# I2C_LCD_Backpack.net
KiCad netlist of a schematic drawn in EAGLE
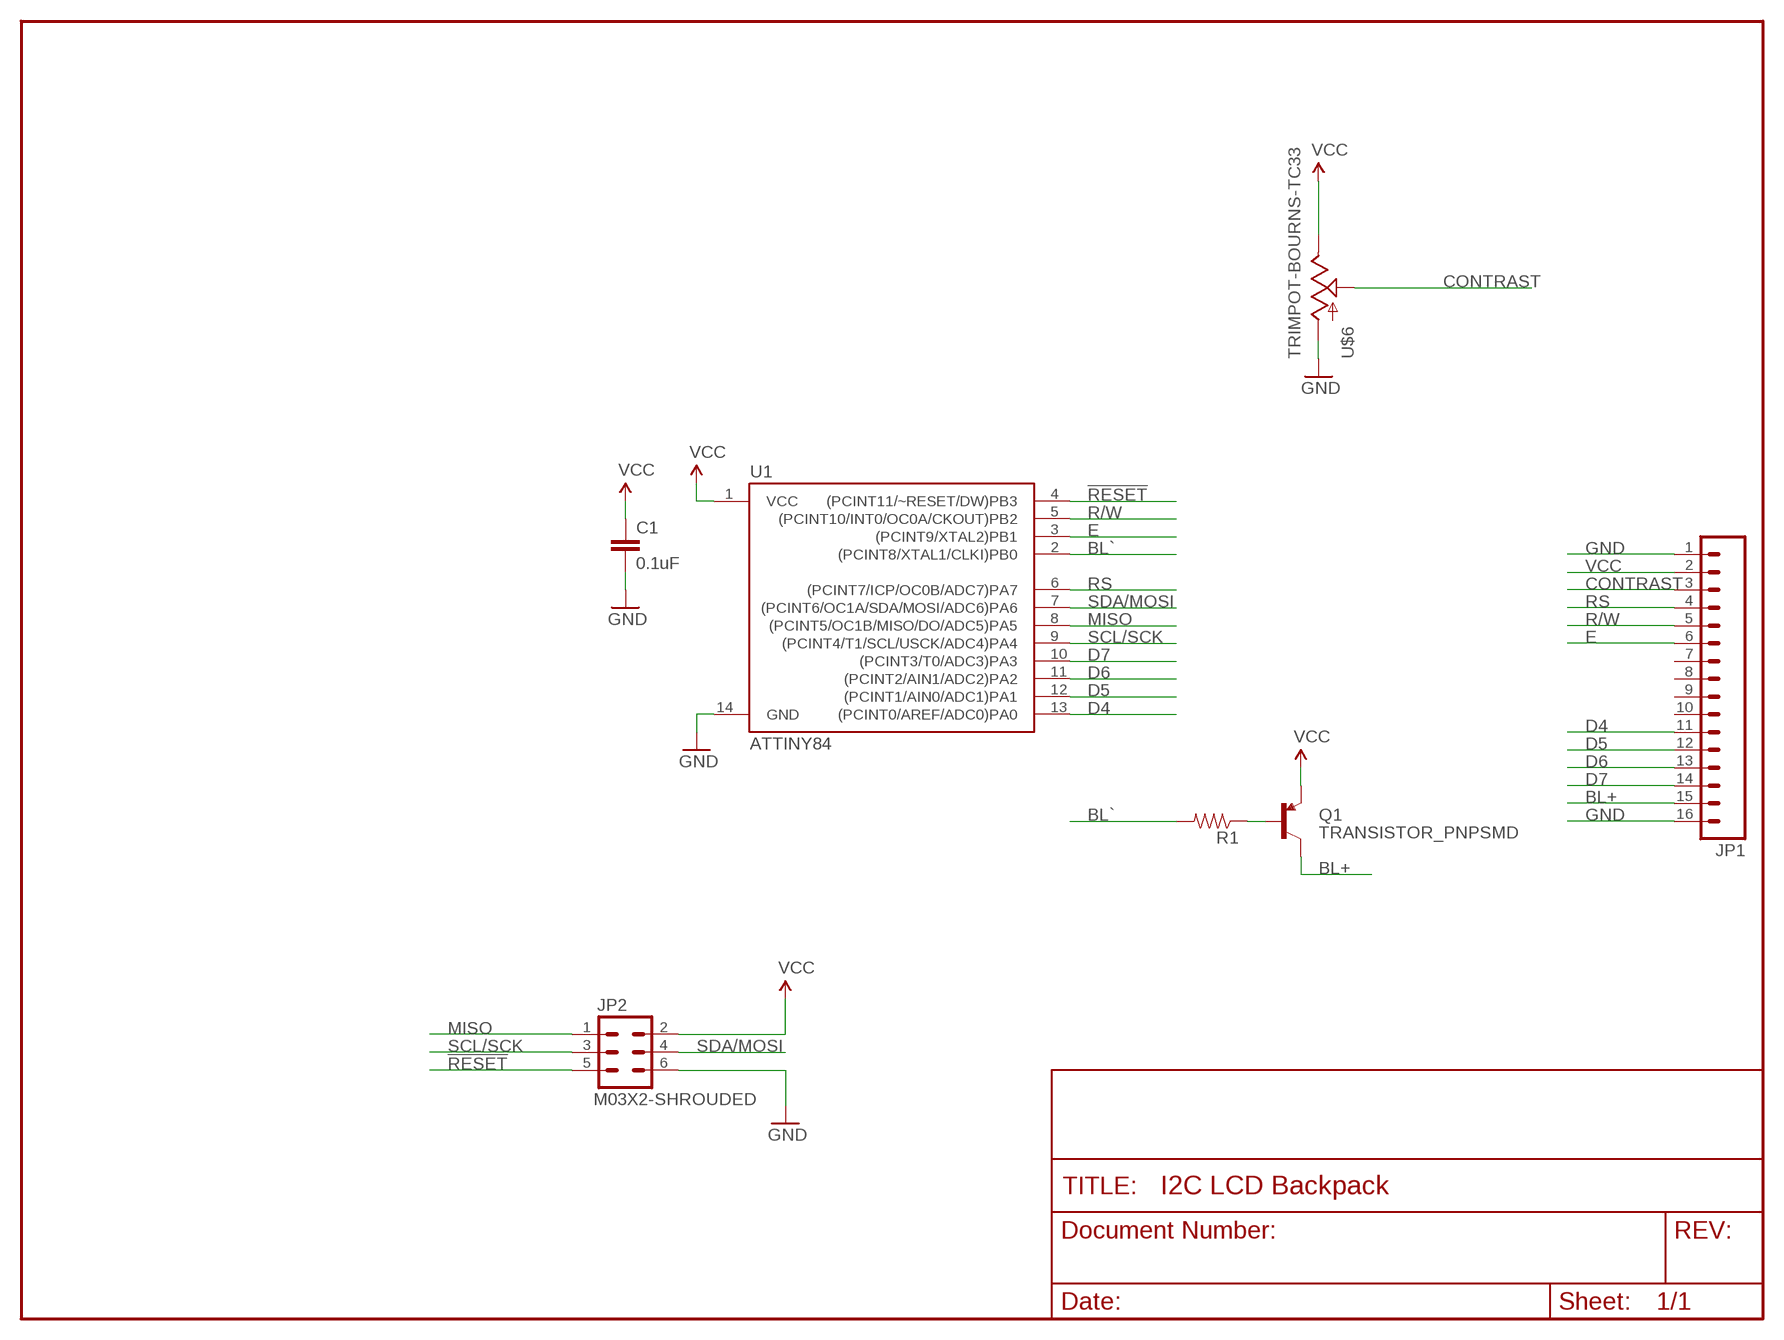
[diagram p0: schematic, sheet 1]

(export (version "E")
  (design (tool "Eeschema 10.0.6"))
  (components
    (comp (ref "C1")
      (value "0.1uF")
      (footprint "eagle-import:0603-CAP")
      (libsource (lib "eagle-import") (part "0.1UF-25V(+80/-20%)(0603)"))
    )
    (comp (ref "JP1")
      (value "M16PTH")
      (footprint "eagle-import:1X16")
      (libsource (lib "eagle-import") (part "M16PTH"))
    )
    (comp (ref "JP2")
      (value "M03X2-SHROUDED")
      (footprint "eagle-import:2X3-SHROUDED-B")
      (libsource (lib "eagle-import") (part "M03X2-SHROUDED"))
    )
    (comp (ref "Q1")
      (value "TRANSISTOR_PNPSMD")
      (footprint "eagle-import:SOT23-3")
      (libsource (lib "eagle-import") (part "TRANSISTOR_PNPSMD"))
    )
    (comp (ref "R1")
      (value "RESISTOR0603-RES")
      (footprint "eagle-import:0603-RES")
      (libsource (lib "eagle-import") (part "RESISTOR0603-RES"))
    )
    (comp (ref "U$6")
      (value "TRIMPOT-BOURNS-TC33")
      (footprint "eagle-import:TRIMPOT-BOURNS-TC33")
      (libsource (lib "eagle-import") (part "TRIMPOT-BOURNS-TC33"))
    )
    (comp (ref "U1")
      (value "ATTINY84")
      (footprint "eagle-import:SO14")
      (libsource (lib "eagle-import") (part "ATTINY84"))
    )
  )
  (nets
    (net (code "1") (name "/BL+") (class "Default")
      (node (ref "JP1") (pin "15") (pinfunction "15_15") (pintype "passive"))
      (node (ref "Q1") (pin "3") (pinfunction "C_3") (pintype "passive"))
    )
    (net (code "2") (name "/BL`") (class "Default")
      (node (ref "R1") (pin "2") (pinfunction "2_2") (pintype "passive"))
      (node (ref "U1") (pin "2") (pinfunction "(PCINT8/XTAL1/CLKI)PB0_2") (pintype "bidirectional"))
    )
    (net (code "3") (name "/CONTRAST") (class "Default")
      (node (ref "JP1") (pin "3") (pinfunction "3_3") (pintype "passive"))
      (node (ref "U$6") (pin "2") (pinfunction "S_2") (pintype "passive"))
    )
    (net (code "4") (name "/D4") (class "Default")
      (node (ref "JP1") (pin "11") (pinfunction "11_11") (pintype "passive"))
      (node (ref "U1") (pin "13") (pinfunction "(PCINT0/AREF/ADC0)PA0_13") (pintype "bidirectional"))
    )
    (net (code "5") (name "/D5") (class "Default")
      (node (ref "JP1") (pin "12") (pinfunction "12_12") (pintype "passive"))
      (node (ref "U1") (pin "12") (pinfunction "(PCINT1/AIN0/ADC1)PA1_12") (pintype "bidirectional"))
    )
    (net (code "6") (name "/D6") (class "Default")
      (node (ref "JP1") (pin "13") (pinfunction "13_13") (pintype "passive"))
      (node (ref "U1") (pin "11") (pinfunction "(PCINT2/AIN1/ADC2)PA2_11") (pintype "bidirectional"))
    )
    (net (code "7") (name "/D7") (class "Default")
      (node (ref "JP1") (pin "14") (pinfunction "14_14") (pintype "passive"))
      (node (ref "U1") (pin "10") (pinfunction "(PCINT3/T0/ADC3)PA3_10") (pintype "bidirectional"))
    )
    (net (code "8") (name "/E") (class "Default")
      (node (ref "JP1") (pin "6") (pinfunction "6_6") (pintype "passive"))
      (node (ref "U1") (pin "3") (pinfunction "(PCINT9/XTAL2)PB1_3") (pintype "bidirectional"))
    )
    (net (code "9") (name "/MISO") (class "Default")
      (node (ref "JP2") (pin "1") (pinfunction "1_1") (pintype "passive"))
      (node (ref "U1") (pin "8") (pinfunction "(PCINT5/OC1B/MISO/DO/ADC5)PA5_8") (pintype "bidirectional"))
    )
    (net (code "10") (name "/RS") (class "Default")
      (node (ref "JP1") (pin "4") (pinfunction "4_4") (pintype "passive"))
      (node (ref "U1") (pin "6") (pinfunction "(PCINT7/ICP/OC0B/ADC7)PA7_6") (pintype "bidirectional"))
    )
    (net (code "11") (name "/R{slash}W") (class "Default")
      (node (ref "JP1") (pin "5") (pinfunction "5_5") (pintype "passive"))
      (node (ref "U1") (pin "5") (pinfunction "(PCINT10/INT0/OC0A/CKOUT)PB2_5") (pintype "bidirectional"))
    )
    (net (code "12") (name "/SCL{slash}SCK") (class "Default")
      (node (ref "JP2") (pin "3") (pinfunction "3_3") (pintype "passive"))
      (node (ref "U1") (pin "9") (pinfunction "(PCINT4/T1/SCL/USCK/ADC4)PA4_9") (pintype "bidirectional"))
    )
    (net (code "13") (name "/SDA{slash}MOSI") (class "Default")
      (node (ref "JP2") (pin "4") (pinfunction "4_4") (pintype "passive"))
      (node (ref "U1") (pin "7") (pinfunction "(PCINT6/OC1A/SDA/MOSI/ADC6)PA6_7") (pintype "bidirectional"))
    )
    (net (code "14") (name "/~{RESET}") (class "Default")
      (node (ref "JP2") (pin "5") (pinfunction "5_5") (pintype "passive"))
      (node (ref "U1") (pin "4") (pinfunction "(PCINT11/~{RESET/DW})PB3_4") (pintype "bidirectional"))
    )
    (net (code "15") (name "GND") (class "Default")
      (node (ref "C1") (pin "2") (pinfunction "2_2") (pintype "passive"))
      (node (ref "JP1") (pin "1") (pinfunction "1_1") (pintype "passive"))
      (node (ref "JP1") (pin "16") (pinfunction "16_16") (pintype "passive"))
      (node (ref "JP2") (pin "6") (pinfunction "6_6") (pintype "passive"))
      (node (ref "U$6") (pin "1") (pinfunction "A_1") (pintype "passive"))
      (node (ref "U1") (pin "14") (pinfunction "GND_14") (pintype "bidirectional"))
    )
    (net (code "16") (name "Net-(Q1-B)") (class "Default")
      (node (ref "Q1") (pin "1") (pinfunction "B_1") (pintype "passive"))
      (node (ref "R1") (pin "1") (pinfunction "1_1") (pintype "passive"))
    )
    (net (code "17") (name "VCC") (class "Default")
      (node (ref "C1") (pin "1") (pinfunction "1_1") (pintype "passive"))
      (node (ref "JP1") (pin "2") (pinfunction "2_2") (pintype "passive"))
      (node (ref "JP2") (pin "2") (pinfunction "2_2") (pintype "passive"))
      (node (ref "Q1") (pin "2") (pinfunction "E_2") (pintype "passive"))
      (node (ref "U$6") (pin "3") (pinfunction "E_3") (pintype "passive"))
      (node (ref "U1") (pin "1") (pinfunction "VCC_1") (pintype "bidirectional"))
    )
    (net (code "18") (name "unconnected-(JP1-Pad7)") (class "Default")
      (node (ref "JP1") (pin "7") (pinfunction "7_7") (pintype "passive"))
    )
    (net (code "19") (name "unconnected-(JP1-Pad8)") (class "Default")
      (node (ref "JP1") (pin "8") (pinfunction "8_8") (pintype "passive"))
    )
    (net (code "20") (name "unconnected-(JP1-Pad9)") (class "Default")
      (node (ref "JP1") (pin "9") (pinfunction "9_9") (pintype "passive"))
    )
    (net (code "21") (name "unconnected-(JP1-Pad10)") (class "Default")
      (node (ref "JP1") (pin "10") (pinfunction "10_10") (pintype "passive"))
    )
  )
)
